# PROC099B_PMIC_Reference.net
KiCad netlist of a schematic drawn in Altium Designer
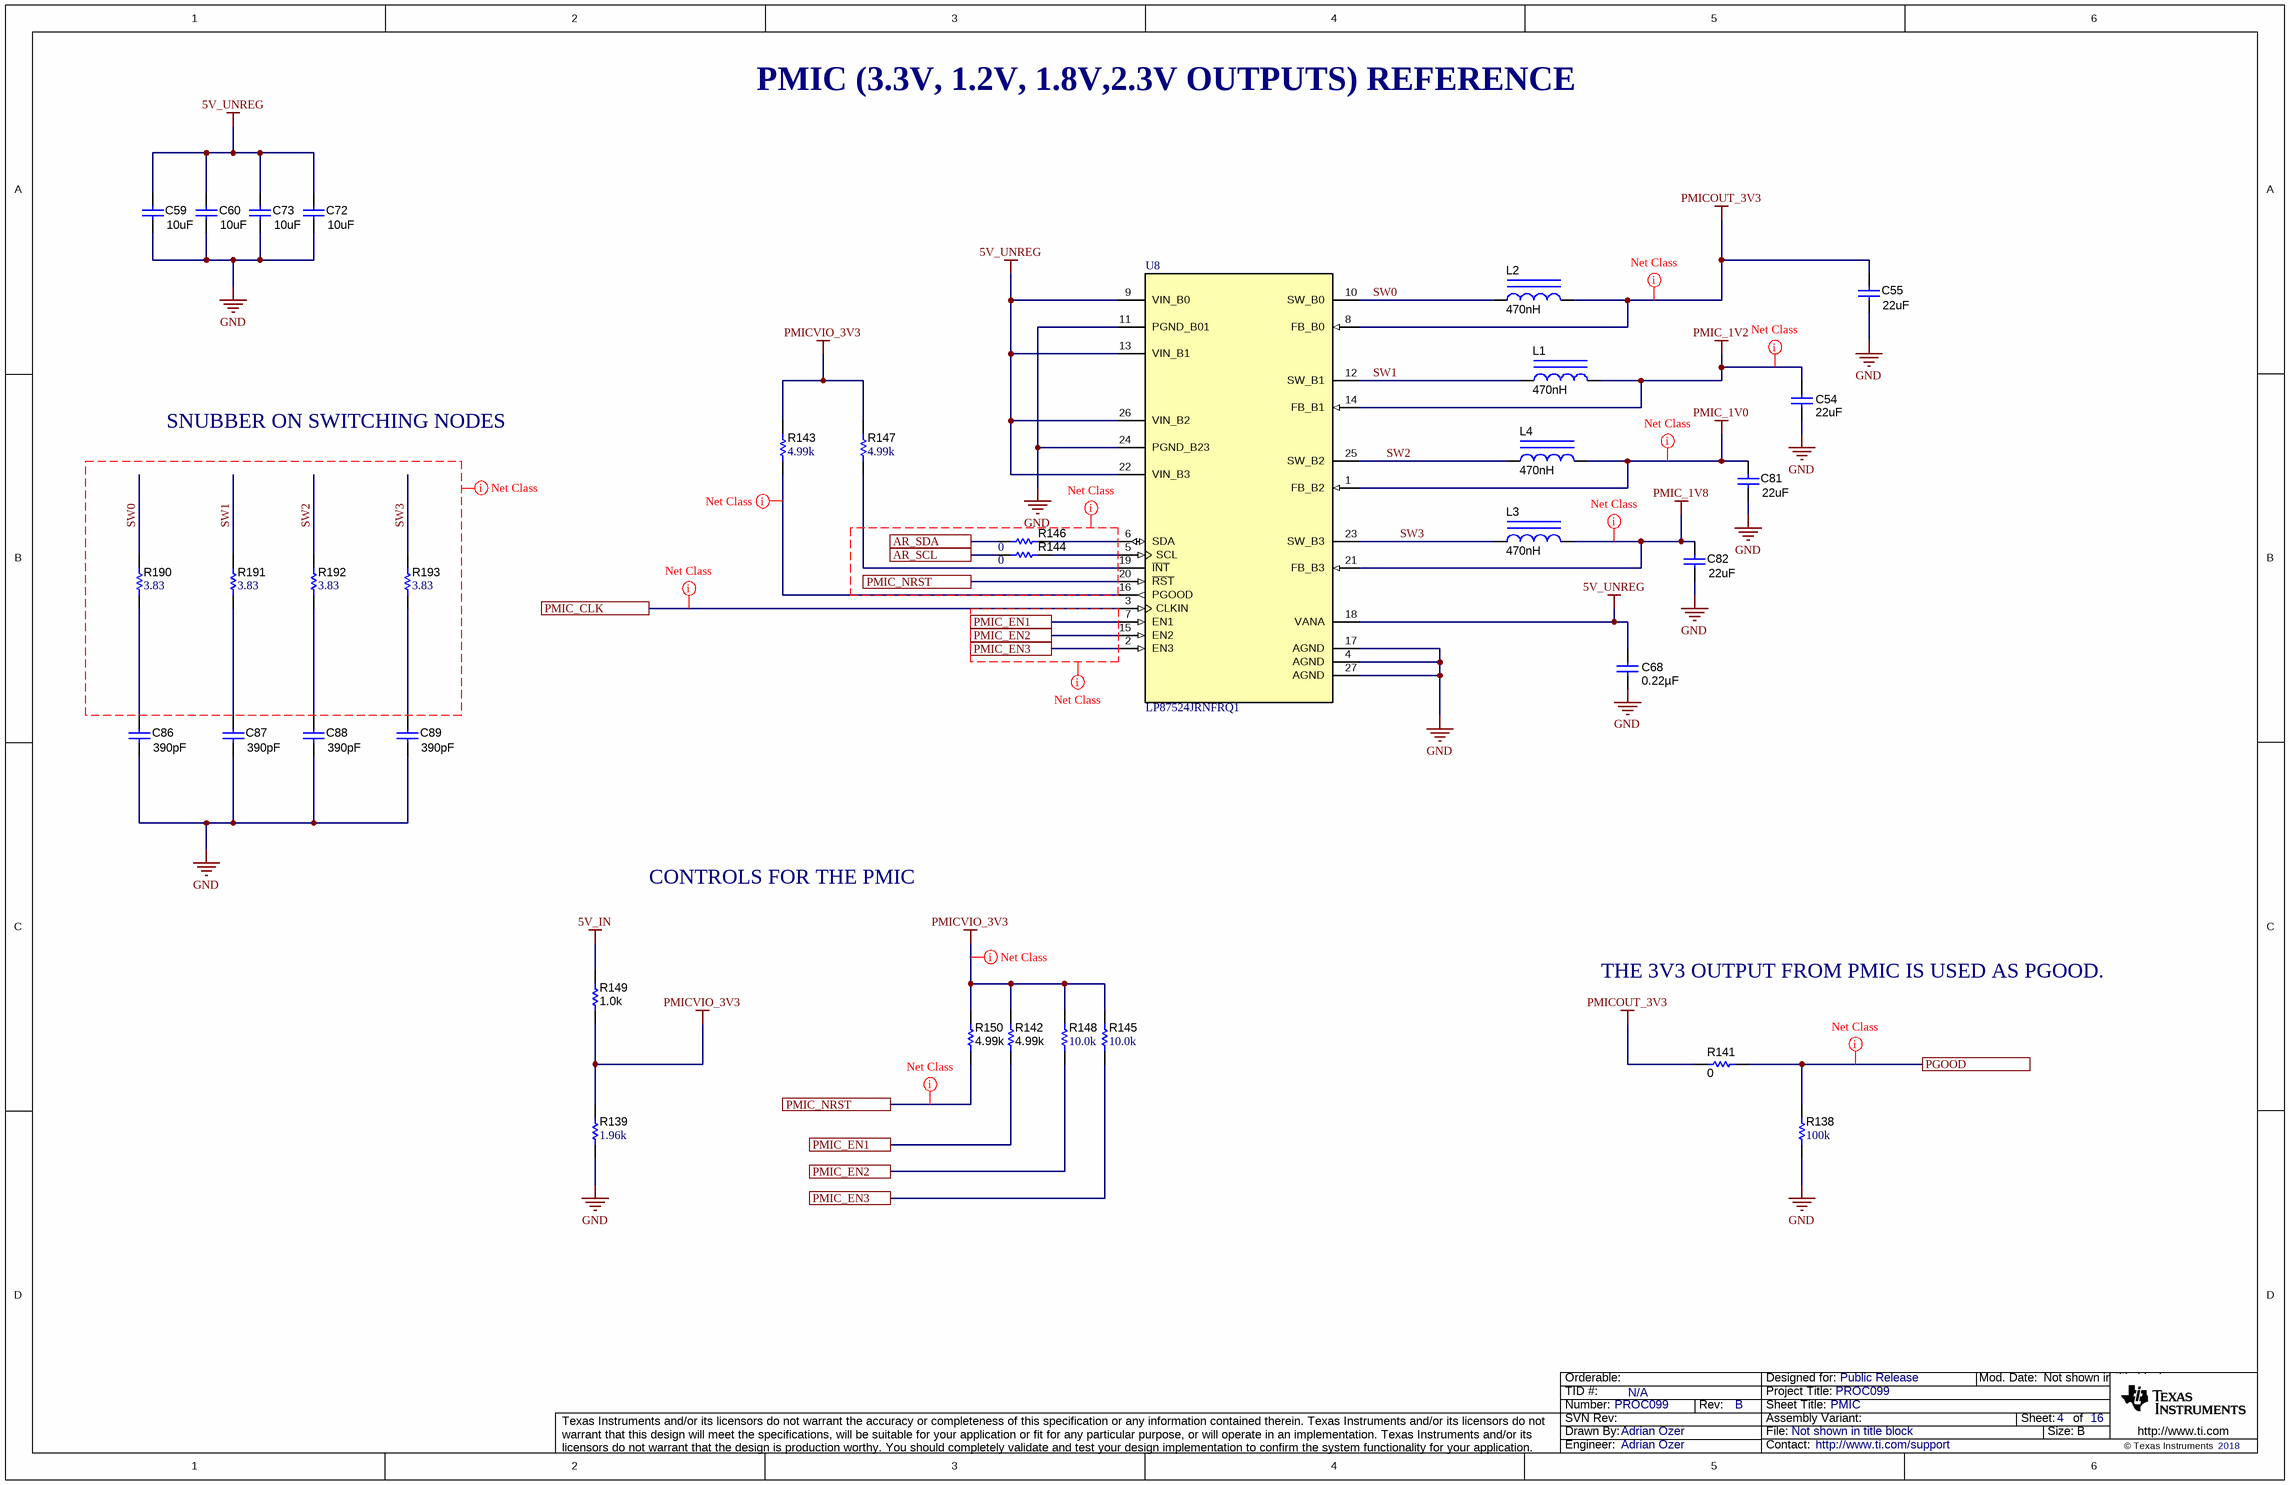
[diagram p0: PROC099B_PMIC_Reference.SchDoc]

(export (version "E")
  (design (tool "Eeschema 10.0.6"))
  (components
    (comp (ref "C54")
      (value "GCM31CR71A226KE02")
      (footprint "1206_180")
      (description "CAP, CERM, 22 uF, 10 V, +/- 10%, X7R, AEC-Q200 Grade 1, 1206")
      (fields
        (field (name "MANUFACTURER") "MuRata")
        (field (name "VALUEDISPLAYED") "22uF")
        (field (name "PUBLISHER") "Texas Instruments")
      )
      (libsource (lib "Altium Vault - TI") (part "CMP-0008811-2"))
    )
    (comp (ref "C55")
      (value "GCM31CR71A226KE02")
      (footprint "1206_180")
      (description "CAP, CERM, 22 uF, 10 V, +/- 10%, X7R, AEC-Q200 Grade 1, 1206")
      (fields
        (field (name "MANUFACTURER") "MuRata")
        (field (name "VALUEDISPLAYED") "22uF")
        (field (name "PUBLISHER") "Texas Instruments")
      )
      (libsource (lib "Altium Vault - TI") (part "Capacitor"))
    )
    (comp (ref "C59")
      (value "GCM21BR71A106KE22L")
      (footprint "0805_HV1")
      (description "CAP, CERM, 10 uF, 10 V, +/- 10%, X7R, 0805")
      (fields
        (field (name "MANUFACTURER") "MuRata")
        (field (name "VALUEDISPLAYED") "10uF")
        (field (name "PUBLISHER") "Texas Instruments")
      )
      (libsource (lib "Altium Vault - TI") (part "CMP-0008017-2"))
    )
    (comp (ref "C60")
      (value "GCM21BR71A106KE22L")
      (footprint "0805_HV1")
      (description "CAP, CERM, 10 uF, 10 V, +/- 10%, X7R, 0805")
      (fields
        (field (name "MANUFACTURER") "MuRata")
        (field (name "VALUEDISPLAYED") "10uF")
        (field (name "PUBLISHER") "Texas Instruments")
      )
      (libsource (lib "Altium Vault - TI") (part "CMP-0008017-2"))
    )
    (comp (ref "C68")
      (value "GCM155R71C224KE02D")
      (footprint "0402L")
      (description "CAP, CERM, 0.22 µF, 16 V,+/- 10%, X7R, AEC-Q200 Grade 1, 0402")
      (fields (field (name "MANUFACTURER") "MuRata") (field (name "VALUEDISPLAYED") "0.22µF"))
      (libsource (lib "Altium Vault - TI") (part "CMP-0078265-1"))
    )
    (comp (ref "C72")
      (value "GCM21BR71A106KE22L")
      (footprint "0805_HV1")
      (description "CAP, CERM, 10 uF, 10 V, +/- 10%, X7R, 0805")
      (fields
        (field (name "MANUFACTURER") "MuRata")
        (field (name "VALUEDISPLAYED") "10uF")
        (field (name "PUBLISHER") "Texas Instruments")
      )
      (libsource (lib "Altium Vault - TI") (part "CMP-0008017-2"))
    )
    (comp (ref "C73")
      (value "GCM21BR71A106KE22L")
      (footprint "0805_HV1")
      (description "CAP, CERM, 10 uF, 10 V, +/- 10%, X7R, 0805")
      (fields
        (field (name "MANUFACTURER") "MuRata")
        (field (name "VALUEDISPLAYED") "10uF")
        (field (name "PUBLISHER") "Texas Instruments")
      )
      (libsource (lib "Altium Vault - TI") (part "CMP-0008017-2"))
    )
    (comp (ref "C81")
      (value "GCM31CR71A226KE02")
      (footprint "1206_180")
      (description "CAP, CERM, 22 uF, 10 V, +/- 10%, X7R, AEC-Q200 Grade 1, 1206")
      (fields
        (field (name "MANUFACTURER") "MuRata")
        (field (name "VALUEDISPLAYED") "22uF")
        (field (name "PUBLISHER") "Texas Instruments")
      )
      (libsource (lib "Altium Vault - TI") (part "Capacitor"))
    )
    (comp (ref "C82")
      (value "GCM31CR71A226KE02")
      (footprint "1206_180")
      (description "CAP, CERM, 22 uF, 10 V, +/- 10%, X7R, AEC-Q200 Grade 1, 1206")
      (fields
        (field (name "MANUFACTURER") "MuRata")
        (field (name "VALUEDISPLAYED") "22uF")
        (field (name "PUBLISHER") "Texas Instruments")
      )
      (libsource (lib "Altium Vault - TI") (part "Capacitor"))
    )
    (comp (ref "C86")
      (value "GRM1555C1H391JA01D")
      (footprint "0402")
      (description "CAP, CERM, 390 pF, 50 V, +/- 5%, C0G/NP0, 0402")
      (fields
        (field (name "MANUFACTURER") "MuRata")
        (field (name "VALUEDISPLAYED") "390pF")
        (field (name "PUBLISHER") "Texas Instruments")
      )
      (libsource (lib "Altium Vault - TI") (part "Capacitor"))
    )
    (comp (ref "C87")
      (value "GRM1555C1H391JA01D")
      (footprint "0402")
      (description "CAP, CERM, 390 pF, 50 V, +/- 5%, C0G/NP0, 0402")
      (fields
        (field (name "MANUFACTURER") "MuRata")
        (field (name "VALUEDISPLAYED") "390pF")
        (field (name "PUBLISHER") "Texas Instruments")
      )
      (libsource (lib "Altium Vault - TI") (part "Capacitor"))
    )
    (comp (ref "C88")
      (value "GRM1555C1H391JA01D")
      (footprint "0402")
      (description "CAP, CERM, 390 pF, 50 V, +/- 5%, C0G/NP0, 0402")
      (fields
        (field (name "MANUFACTURER") "MuRata")
        (field (name "VALUEDISPLAYED") "390pF")
        (field (name "PUBLISHER") "Texas Instruments")
      )
      (libsource (lib "Altium Vault - TI") (part "Capacitor"))
    )
    (comp (ref "C89")
      (value "GRM1555C1H391JA01D")
      (footprint "0402")
      (description "CAP, CERM, 390 pF, 50 V, +/- 5%, C0G/NP0, 0402")
      (fields
        (field (name "MANUFACTURER") "MuRata")
        (field (name "VALUEDISPLAYED") "390pF")
        (field (name "PUBLISHER") "Texas Instruments")
      )
      (libsource (lib "Altium Vault - TI") (part "Capacitor"))
    )
    (comp (ref "L1")
      (value "DFE252012P-R47M=P2")
      (footprint "DFE252012P")
      (description "Inductor, Shielded, 470 nH, 4.7 A, 0.021 ohm, SMD")
      (fields
        (field (name "MANUFACTURER") "MuRata Toko")
        (field (name "VALUEDISPLAYED") "470nH")
        (field (name "PUBLISHER") "Texas Instruments")
      )
      (libsource (lib "Altium Vault - TI") (part "Inductor_Iron"))
    )
    (comp (ref "L2")
      (value "DFE252012P-R47M=P2")
      (footprint "DFE252012P")
      (description "Inductor, Shielded, 470 nH, 4.7 A, 0.021 ohm, SMD")
      (fields
        (field (name "MANUFACTURER") "MuRata Toko")
        (field (name "VALUEDISPLAYED") "470nH")
        (field (name "PUBLISHER") "Texas Instruments")
      )
      (libsource (lib "Altium Vault - TI") (part "Inductor_Iron"))
    )
    (comp (ref "L3")
      (value "DFE252012P-R47M=P2")
      (footprint "DFE252012P")
      (description "Inductor, Shielded, 470 nH, 4.7 A, 0.021 ohm, SMD")
      (fields
        (field (name "MANUFACTURER") "MuRata Toko")
        (field (name "VALUEDISPLAYED") "470nH")
        (field (name "PUBLISHER") "Texas Instruments")
      )
      (libsource (lib "Altium Vault - TI") (part "Inductor_Iron"))
    )
    (comp (ref "L4")
      (value "DFE252012P-R47M=P2")
      (footprint "DFE252012P")
      (description "Inductor, Shielded, 470 nH, 4.7 A, 0.021 ohm, SMD")
      (fields
        (field (name "MANUFACTURER") "MuRata Toko")
        (field (name "VALUEDISPLAYED") "470nH")
        (field (name "PUBLISHER") "Texas Instruments")
      )
      (libsource (lib "Altium Vault - TI") (part "Inductor_Iron"))
    )
    (comp (ref "R138")
      (value "CRCW0402100KFKED")
      (footprint "0402L")
      (description "RES, 100 k, 1%, 0.063 W, AEC-Q200 Grade 0, 0402")
      (fields (field (name "MANUFACTURER") "Vishay-Dale") (field (name "VALUEDISPLAYED") "100k"))
      (libsource (lib "Altium Vault - TI") (part "Resistor"))
    )
    (comp (ref "R139")
      (value "CRCW04021K96FKED")
      (footprint "0402L")
      (description "RES, 1.96 k, 1%, 0.063 W, AEC-Q200 Grade 0, 0402")
      (fields (field (name "MANUFACTURER") "Vishay-Dale") (field (name "VALUEDISPLAYED") "1.96k"))
      (libsource (lib "Altium Vault - TI") (part "Resistor"))
    )
    (comp (ref "R141")
      (value "ERJ-2GE0R00X")
      (footprint "0402L")
      (description "RES, 0, 5%, 0.063 W, 0402")
      (fields
        (field (name "MANUFACTURER") "Panasonic")
        (field (name "VALUEDISPLAYED") "0")
        (field (name "PUBLISHER") "Texas Instruments")
      )
      (libsource (lib "Altium Vault - TI") (part "Resistor"))
    )
    (comp (ref "R142")
      (value "ERJ-2RKF4991X")
      (footprint "0402L")
      (description "RES, 4.99 k, 1%, 0.1 W, AEC-Q200 Grade 0, 0402")
      (fields
        (field (name "MANUFACTURER") "Panasonic")
        (field (name "VALUEDISPLAYED") "4.99k")
        (field (name "PUBLISHER") "Texas Instruments")
      )
      (libsource (lib "Altium Vault - TI") (part "Resistor"))
    )
    (comp (ref "R143")
      (value "CRCW04024K99FKED")
      (footprint "0402L")
      (description "RES, 4.99 k, 1%, 0.063 W, AEC-Q200 Grade 0, 0402")
      (fields (field (name "MANUFACTURER") "Vishay-Dale") (field (name "VALUEDISPLAYED") "4.99k"))
      (libsource (lib "Altium Vault - TI") (part "Resistor"))
    )
    (comp (ref "R144")
      (value "CRCW02010000Z0ED")
      (footprint "0201_Silk")
      (description "RES, 0, 5%, 0.05 W, 0201")
      (fields (field (name "MANUFACTURER") "Vishay-Dale") (field (name "VALUEDISPLAYED") "0"))
      (libsource (lib "Altium Vault - TI") (part "Resistor"))
    )
    (comp (ref "R145")
      (value "CRCW040210K0FKED")
      (footprint "0402L")
      (description "RES, 10.0 k, 1%, 0.063 W, AEC-Q200 Grade 0, 0402")
      (fields (field (name "MANUFACTURER") "Vishay-Dale") (field (name "VALUEDISPLAYED") "10.0k"))
      (libsource (lib "Altium Vault - TI") (part "CMP-0025958-3"))
    )
    (comp (ref "R146")
      (value "CRCW02010000Z0ED")
      (footprint "0201_Silk")
      (description "RES, 0, 5%, 0.05 W, 0201")
      (fields (field (name "MANUFACTURER") "Vishay-Dale") (field (name "VALUEDISPLAYED") "0"))
      (libsource (lib "Altium Vault - TI") (part "Resistor"))
    )
    (comp (ref "R147")
      (value "CRCW04024K99FKED")
      (footprint "0402L")
      (description "RES, 4.99 k, 1%, 0.063 W, AEC-Q200 Grade 0, 0402")
      (fields (field (name "MANUFACTURER") "Vishay-Dale") (field (name "VALUEDISPLAYED") "4.99k"))
      (libsource (lib "Altium Vault - TI") (part "Resistor"))
    )
    (comp (ref "R148")
      (value "CRCW040210K0FKED")
      (footprint "0402L")
      (description "RES, 10.0 k, 1%, 0.063 W, AEC-Q200 Grade 0, 0402")
      (fields (field (name "MANUFACTURER") "Vishay-Dale") (field (name "VALUEDISPLAYED") "10.0k"))
      (libsource (lib "Altium Vault - TI") (part "Resistor"))
    )
    (comp (ref "R149")
      (value "ERJ-2GEJ102X")
      (footprint "0402L")
      (description "RES, 1.0 k, 5%, 0.1 W, AEC-Q200 Grade 0, 0402")
      (fields (field (name "MANUFACTURER") "Panasonic") (field (name "VALUEDISPLAYED") "1.0k"))
      (libsource (lib "Altium Vault - TI") (part "Resistor"))
    )
    (comp (ref "R150")
      (value "ERJ-2RKF4991X")
      (footprint "0402L")
      (description "RES, 4.99 k, 1%, 0.1 W, AEC-Q200 Grade 0, 0402")
      (fields
        (field (name "MANUFACTURER") "Panasonic")
        (field (name "VALUEDISPLAYED") "4.99k")
        (field (name "PUBLISHER") "Texas Instruments")
      )
      (libsource (lib "Altium Vault - TI") (part "Resistor"))
    )
    (comp (ref "R190")
      (value "CRCW04023R83FKED")
      (footprint "0402L")
      (description "RES, 3.83, 1%, 0.063 W, AEC-Q200 Grade 0, 0402")
      (fields (field (name "MANUFACTURER") "Vishay-Dale") (field (name "VALUEDISPLAYED") "3.83"))
      (libsource (lib "Altium Vault - TI") (part "Resistor"))
    )
    (comp (ref "R191")
      (value "CRCW04023R83FKED")
      (footprint "0402L")
      (description "RES, 3.83, 1%, 0.063 W, AEC-Q200 Grade 0, 0402")
      (fields (field (name "MANUFACTURER") "Vishay-Dale") (field (name "VALUEDISPLAYED") "3.83"))
      (libsource (lib "Altium Vault - TI") (part "Resistor"))
    )
    (comp (ref "R192")
      (value "CRCW04023R83FKED")
      (footprint "0402L")
      (description "RES, 3.83, 1%, 0.063 W, AEC-Q200 Grade 0, 0402")
      (fields (field (name "MANUFACTURER") "Vishay-Dale") (field (name "VALUEDISPLAYED") "3.83"))
      (libsource (lib "Altium Vault - TI") (part "Resistor"))
    )
    (comp (ref "R193")
      (value "CRCW04023R83FKED")
      (footprint "0402L")
      (description "RES, 3.83, 1%, 0.063 W, AEC-Q200 Grade 0, 0402")
      (fields (field (name "MANUFACTURER") "Vishay-Dale") (field (name "VALUEDISPLAYED") "3.83"))
      (libsource (lib "Altium Vault - TI") (part "Resistor"))
    )
    (comp (ref "U8")
      (value "LP87524JRNFRQ1")
      (footprint "RNF0026C")
      (description "4-A + 2.5-A + Two 1.5-A Buck Converters With Integrated Switches, RNF0026C (VQFN-HR-26)")
      (fields
        (field (name "ALTERNATE PARTNUMBER") "LP87524JRNFTQ1")
        (field (name "MANUFACTURER") "Texas Instruments")
        (field (name "PARTNUMBER") "LP87524JRNFRQ1")
      )
      (libsource (lib "Altium Vault - TI") (part "CMP-0079120-1"))
    )
  )
  (nets
    (net (code "1") (name "/AR_SCL") (class "Default")
      (node (ref "R144") (pin "1") (pinfunction "1_1") (pintype "passive"))
    )
    (net (code "2") (name "/AR_SDA") (class "Default")
      (node (ref "R146") (pin "2") (pinfunction "2_2") (pintype "passive"))
    )
    (net (code "3") (name "/PGOOD") (class "Default")
      (node (ref "R138") (pin "2") (pinfunction "2_2") (pintype "passive"))
      (node (ref "R141") (pin "2") (pinfunction "2_2") (pintype "passive"))
    )
    (net (code "4") (name "/PMIC_CLK") (class "Default")
      (node (ref "U8") (pin "3") (pinfunction "CLKIN_3") (pintype "input"))
    )
    (net (code "5") (name "/PMIC_EN1") (class "Default")
      (node (ref "R142") (pin "1") (pinfunction "1_1") (pintype "passive"))
      (node (ref "U8") (pin "7") (pinfunction "EN1_7") (pintype "input"))
    )
    (net (code "6") (name "/PMIC_EN2") (class "Default")
      (node (ref "R148") (pin "1") (pinfunction "1_1") (pintype "passive"))
      (node (ref "U8") (pin "15") (pinfunction "EN2_15") (pintype "input"))
    )
    (net (code "7") (name "/PMIC_EN3") (class "Default")
      (node (ref "R145") (pin "1") (pinfunction "1_1") (pintype "passive"))
      (node (ref "U8") (pin "2") (pinfunction "EN3_2") (pintype "input"))
    )
    (net (code "8") (name "/PMIC_NRST") (class "Default")
      (node (ref "R150") (pin "2") (pinfunction "2_2") (pintype "passive"))
      (node (ref "U8") (pin "20") (pinfunction "RST_20") (pintype "input"))
    )
    (net (code "9") (name "/SW0") (class "Default")
      (node (ref "L2") (pin "1") (pinfunction "1_1") (pintype "passive"))
      (node (ref "R190") (pin "2") (pinfunction "2_2") (pintype "passive"))
      (node (ref "U8") (pin "10") (pinfunction "SW_B0_10") (pintype "power_in"))
    )
    (net (code "10") (name "/SW1") (class "Default")
      (node (ref "L1") (pin "1") (pinfunction "1_1") (pintype "passive"))
      (node (ref "R191") (pin "2") (pinfunction "2_2") (pintype "passive"))
      (node (ref "U8") (pin "12") (pinfunction "SW_B1_12") (pintype "power_in"))
    )
    (net (code "11") (name "/SW2") (class "Default")
      (node (ref "L4") (pin "1") (pinfunction "1_1") (pintype "passive"))
      (node (ref "R192") (pin "2") (pinfunction "2_2") (pintype "passive"))
      (node (ref "U8") (pin "25") (pinfunction "SW_B2_25") (pintype "power_in"))
    )
    (net (code "12") (name "/SW3") (class "Default")
      (node (ref "L3") (pin "1") (pinfunction "1_1") (pintype "passive"))
      (node (ref "R193") (pin "2") (pinfunction "2_2") (pintype "passive"))
      (node (ref "U8") (pin "23") (pinfunction "SW_B3_23") (pintype "power_in"))
    )
    (net (code "13") (name "5V_IN") (class "Default")
      (node (ref "R149") (pin "2") (pinfunction "2_2") (pintype "passive"))
    )
    (net (code "14") (name "5V_UNREG") (class "Default")
      (node (ref "C59") (pin "2") (pinfunction "2_2") (pintype "passive"))
      (node (ref "C60") (pin "2") (pinfunction "2_2") (pintype "passive"))
      (node (ref "C68") (pin "2") (pinfunction "2_2") (pintype "passive"))
      (node (ref "C72") (pin "2") (pinfunction "2_2") (pintype "passive"))
      (node (ref "C73") (pin "2") (pinfunction "2_2") (pintype "passive"))
      (node (ref "U8") (pin "13") (pinfunction "VIN_B1_13") (pintype "power_in"))
      (node (ref "U8") (pin "18") (pinfunction "VANA_18") (pintype "power_in"))
      (node (ref "U8") (pin "22") (pinfunction "VIN_B3_22") (pintype "power_in"))
      (node (ref "U8") (pin "26") (pinfunction "VIN_B2_26") (pintype "power_in"))
      (node (ref "U8") (pin "9") (pinfunction "VIN_B0_9") (pintype "power_in"))
    )
    (net (code "15") (name "GND") (class "Default")
      (node (ref "C54") (pin "1") (pinfunction "1_1") (pintype "passive"))
      (node (ref "C55") (pin "1") (pinfunction "1_1") (pintype "passive"))
      (node (ref "C59") (pin "1") (pinfunction "1_1") (pintype "passive"))
      (node (ref "C60") (pin "1") (pinfunction "1_1") (pintype "passive"))
      (node (ref "C68") (pin "1") (pinfunction "1_1") (pintype "passive"))
      (node (ref "C72") (pin "1") (pinfunction "1_1") (pintype "passive"))
      (node (ref "C73") (pin "1") (pinfunction "1_1") (pintype "passive"))
      (node (ref "C81") (pin "1") (pinfunction "1_1") (pintype "passive"))
      (node (ref "C82") (pin "1") (pinfunction "1_1") (pintype "passive"))
      (node (ref "C86") (pin "2") (pinfunction "2_2") (pintype "passive"))
      (node (ref "C87") (pin "2") (pinfunction "2_2") (pintype "passive"))
      (node (ref "C88") (pin "2") (pinfunction "2_2") (pintype "passive"))
      (node (ref "C89") (pin "2") (pinfunction "2_2") (pintype "passive"))
      (node (ref "R138") (pin "1") (pinfunction "1_1") (pintype "passive"))
      (node (ref "R139") (pin "1") (pinfunction "1_1") (pintype "passive"))
      (node (ref "U8") (pin "11") (pinfunction "PGND_B01_11") (pintype "power_in"))
      (node (ref "U8") (pin "17") (pinfunction "AGND_17") (pintype "power_in"))
      (node (ref "U8") (pin "24") (pinfunction "PGND_B23_24") (pintype "power_in"))
      (node (ref "U8") (pin "27") (pinfunction "AGND_27") (pintype "power_in"))
      (node (ref "U8") (pin "4") (pinfunction "AGND_4") (pintype "power_in"))
    )
    (net (code "16") (name "Net-(C86-Pad1)") (class "Default")
      (node (ref "C86") (pin "1") (pinfunction "1_1") (pintype "passive"))
      (node (ref "R190") (pin "1") (pinfunction "1_1") (pintype "passive"))
    )
    (net (code "17") (name "Net-(C87-Pad1)") (class "Default")
      (node (ref "C87") (pin "1") (pinfunction "1_1") (pintype "passive"))
      (node (ref "R191") (pin "1") (pinfunction "1_1") (pintype "passive"))
    )
    (net (code "18") (name "Net-(C88-Pad1)") (class "Default")
      (node (ref "C88") (pin "1") (pinfunction "1_1") (pintype "passive"))
      (node (ref "R192") (pin "1") (pinfunction "1_1") (pintype "passive"))
    )
    (net (code "19") (name "Net-(C89-Pad1)") (class "Default")
      (node (ref "C89") (pin "1") (pinfunction "1_1") (pintype "passive"))
      (node (ref "R193") (pin "1") (pinfunction "1_1") (pintype "passive"))
    )
    (net (code "20") (name "Net-(U8-INT)") (class "Default")
      (node (ref "R147") (pin "1") (pinfunction "1_1") (pintype "passive"))
      (node (ref "U8") (pin "19") (pinfunction "INT_19") (pintype "open_collector"))
    )
    (net (code "21") (name "Net-(U8-PGOOD)") (class "Default")
      (node (ref "R143") (pin "1") (pinfunction "1_1") (pintype "passive"))
      (node (ref "U8") (pin "16") (pinfunction "PGOOD_16") (pintype "output"))
    )
    (net (code "22") (name "Net-(U8-SCL)") (class "Default")
      (node (ref "R144") (pin "2") (pinfunction "2_2") (pintype "passive"))
      (node (ref "U8") (pin "5") (pinfunction "SCL_5") (pintype "input"))
    )
    (net (code "23") (name "Net-(U8-SDA)") (class "Default")
      (node (ref "R146") (pin "1") (pinfunction "1_1") (pintype "passive"))
      (node (ref "U8") (pin "6") (pinfunction "SDA_6") (pintype "bidirectional"))
    )
    (net (code "24") (name "PMICOUT_3V3") (class "Default")
      (node (ref "C55") (pin "2") (pinfunction "2_2") (pintype "passive"))
      (node (ref "L2") (pin "2") (pinfunction "2_2") (pintype "passive"))
      (node (ref "R141") (pin "1") (pinfunction "1_1") (pintype "passive"))
      (node (ref "U8") (pin "8") (pinfunction "FB_B0_8") (pintype "input"))
    )
    (net (code "25") (name "PMICVIO_3V3") (class "Default")
      (node (ref "R139") (pin "2") (pinfunction "2_2") (pintype "passive"))
      (node (ref "R142") (pin "2") (pinfunction "2_2") (pintype "passive"))
      (node (ref "R143") (pin "2") (pinfunction "2_2") (pintype "passive"))
      (node (ref "R145") (pin "2") (pinfunction "2_2") (pintype "passive"))
      (node (ref "R147") (pin "2") (pinfunction "2_2") (pintype "passive"))
      (node (ref "R148") (pin "2") (pinfunction "2_2") (pintype "passive"))
      (node (ref "R149") (pin "1") (pinfunction "1_1") (pintype "passive"))
      (node (ref "R150") (pin "1") (pinfunction "1_1") (pintype "passive"))
    )
    (net (code "26") (name "PMIC_1V0") (class "Default")
      (node (ref "C81") (pin "2") (pinfunction "2_2") (pintype "passive"))
      (node (ref "L4") (pin "2") (pinfunction "2_2") (pintype "passive"))
      (node (ref "U8") (pin "1") (pinfunction "FB_B2_1") (pintype "input"))
    )
    (net (code "27") (name "PMIC_1V2") (class "Default")
      (node (ref "C54") (pin "2") (pinfunction "2_2") (pintype "passive"))
      (node (ref "L1") (pin "2") (pinfunction "2_2") (pintype "passive"))
      (node (ref "U8") (pin "14") (pinfunction "FB_B1_14") (pintype "input"))
    )
    (net (code "28") (name "PMIC_1V8") (class "Default")
      (node (ref "C82") (pin "2") (pinfunction "2_2") (pintype "passive"))
      (node (ref "L3") (pin "2") (pinfunction "2_2") (pintype "passive"))
      (node (ref "U8") (pin "21") (pinfunction "FB_B3_21") (pintype "input"))
    )
  )
)
